# Sheet1.net
KiCad netlist of a schematic drawn in Altium Designer
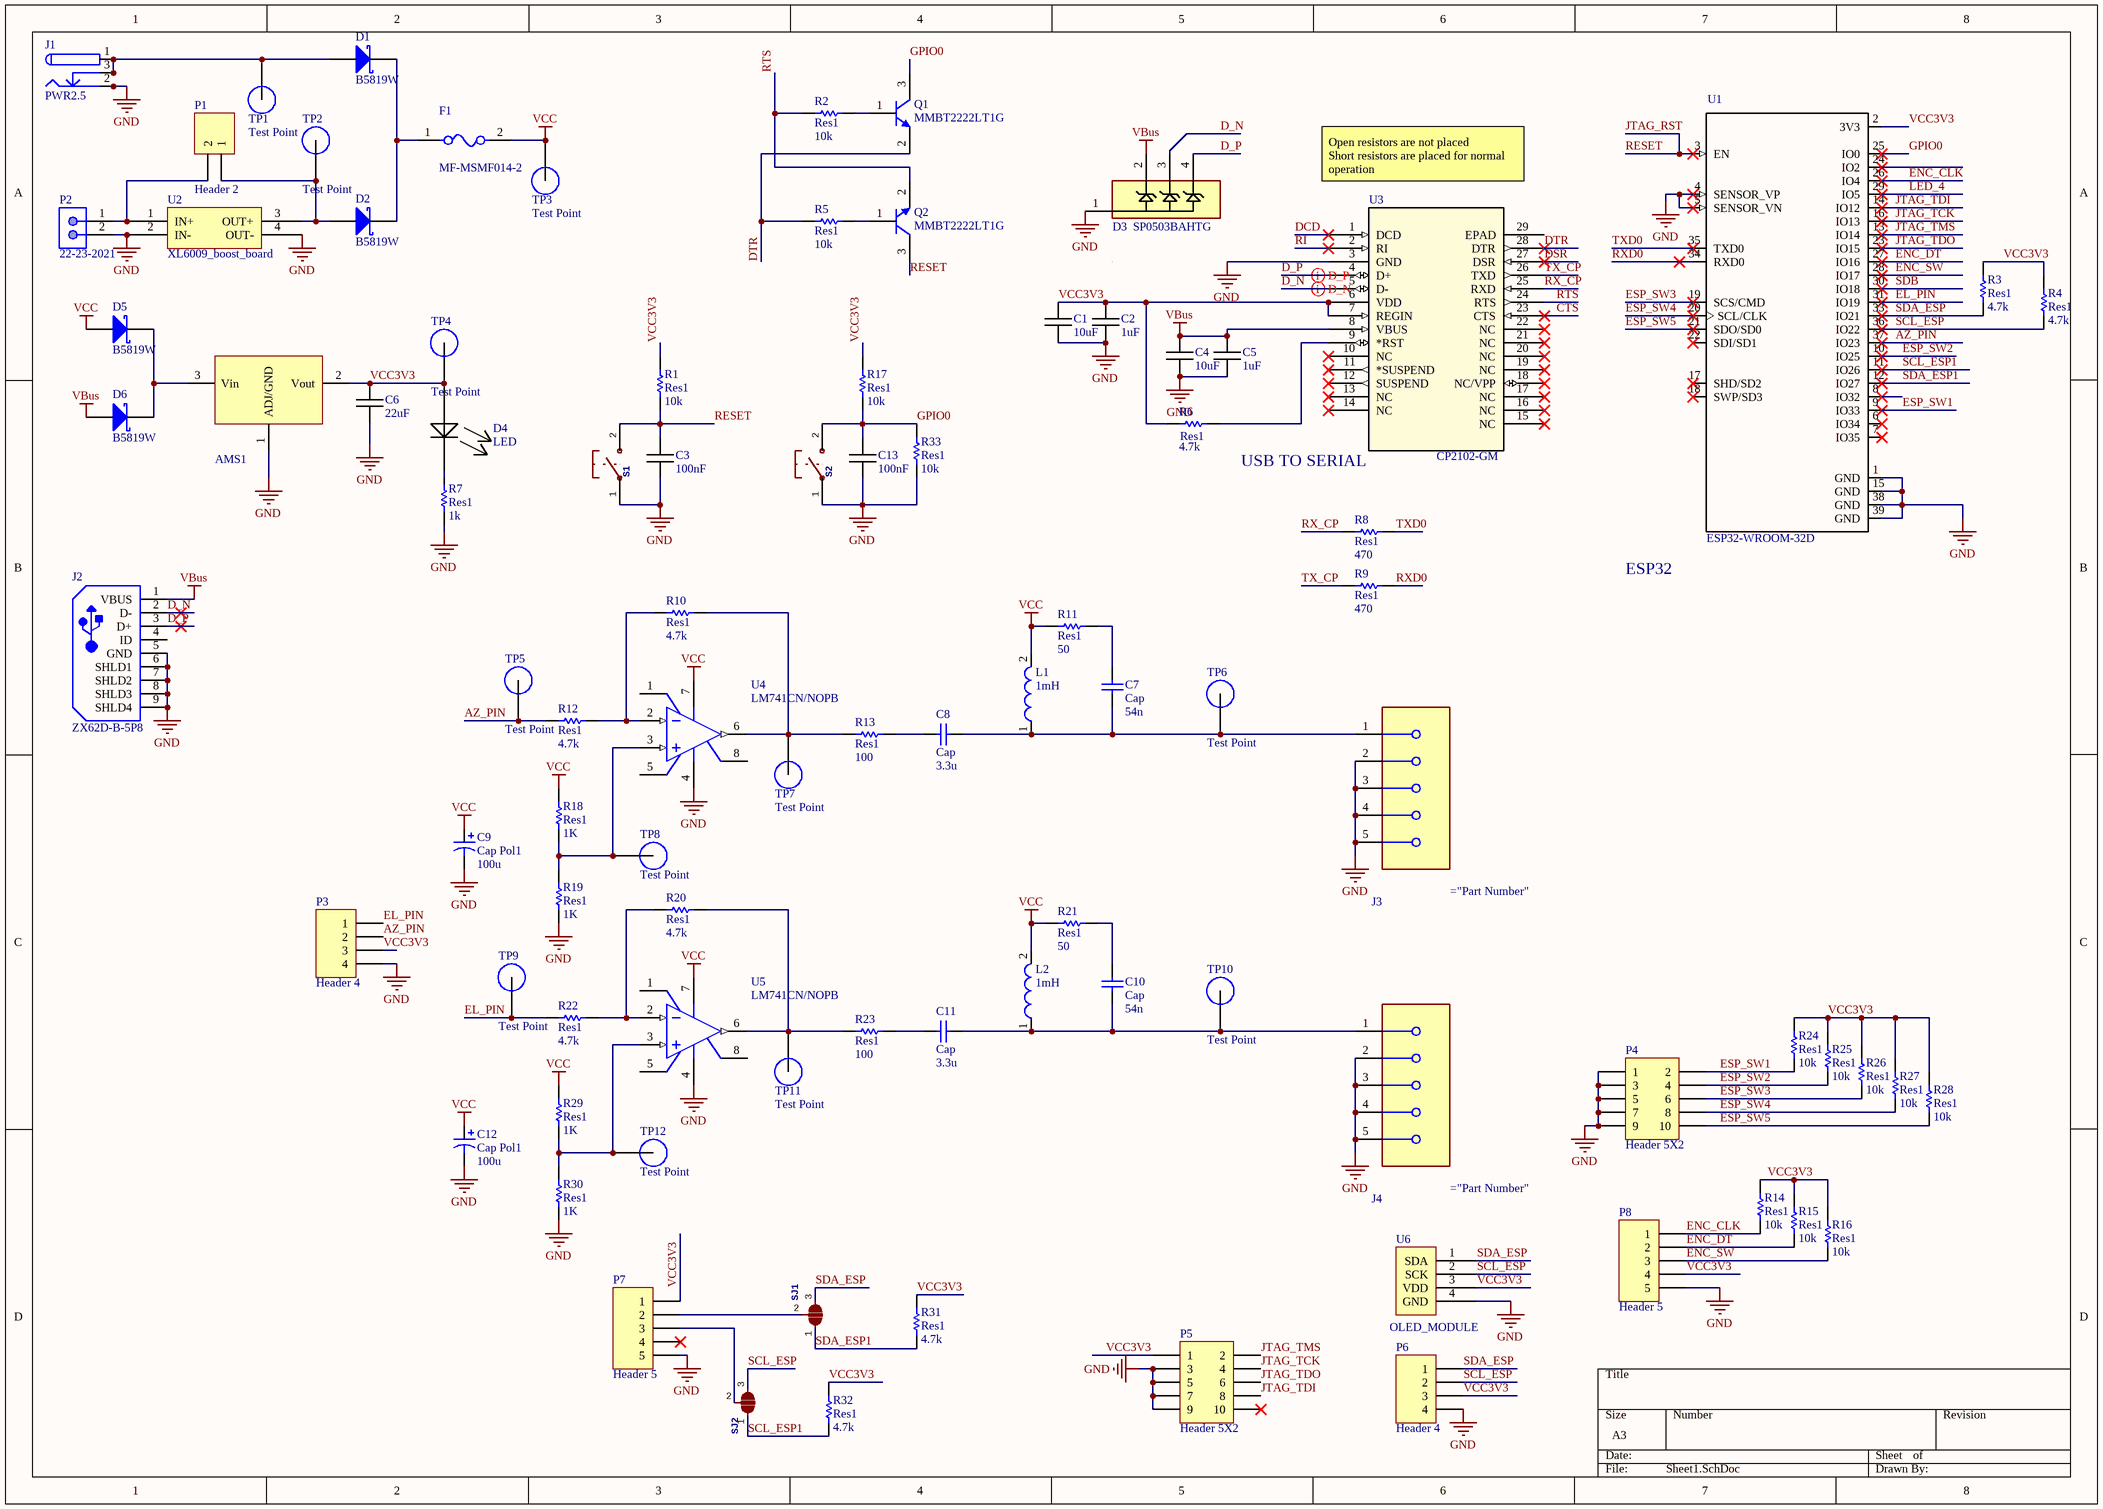
[diagram p0: Sheet1.SchDoc]

(export (version "E")
  (design (tool "Eeschema 10.0.6"))
  (components
    (comp (ref "AMS1")
      (value "AMS1117")
      (footprint "SOT-223-3")
      (description "LDO 3.3V/5V/12V")
      (libsource (lib "IC") (part "AMS1117"))
    )
    (comp (ref "C1")
      (value "10uF")
      (footprint "C 0603 / 1608")
      (libsource (lib "Standard") (part "Capacitor"))
    )
    (comp (ref "C2")
      (value "1uF")
      (footprint "C 0603 / 1608")
      (libsource (lib "Standard") (part "Capacitor"))
    )
    (comp (ref "C3")
      (value "100nF")
      (footprint "C 0603 / 1608")
      (libsource (lib "Standard") (part "Capacitor"))
    )
    (comp (ref "C4")
      (value "10uF")
      (footprint "C 0603 / 1608")
      (libsource (lib "Standard") (part "Capacitor"))
    )
    (comp (ref "C5")
      (value "1uF")
      (footprint "C 0603 / 1608")
      (libsource (lib "Standard") (part "Capacitor"))
    )
    (comp (ref "C6")
      (value "22uF")
      (footprint "C 0603 / 1608")
      (libsource (lib "Standard") (part "Capacitor"))
    )
    (comp (ref "C7")
      (value "Cap")
      (footprint "C 0603 / 1608")
      (description "Capacitor")
      (fields (field (name "ALTIUM_VALUE") "54n") (field (name "PUBLISHER") "Altium Limited"))
      (libsource (lib "Standard") (part "Cap"))
    )
    (comp (ref "C8")
      (value "Cap")
      (footprint "C 0603 / 1608")
      (description "Capacitor")
      (fields (field (name "ALTIUM_VALUE") "3.3u") (field (name "PUBLISHER") "Altium Limited"))
      (libsource (lib "Standard") (part "Cap"))
    )
    (comp (ref "C9")
      (value "Cap Pol1")
      (footprint "CAP0603R")
      (description "Polarized Capacitor (Radial)")
      (fields (field (name "ALTIUM_VALUE") "100u") (field (name "PUBLISHER") "Altium Limited"))
      (libsource (lib "Miscellaneous Devices") (part "Cap Pol1"))
    )
    (comp (ref "C10")
      (value "Cap")
      (footprint "C 0603 / 1608")
      (description "Capacitor")
      (fields (field (name "ALTIUM_VALUE") "54n") (field (name "PUBLISHER") "Altium Limited"))
      (libsource (lib "Standard") (part "Cap"))
    )
    (comp (ref "C11")
      (value "Cap")
      (footprint "C 0603 / 1608")
      (description "Capacitor")
      (fields (field (name "ALTIUM_VALUE") "3.3u") (field (name "PUBLISHER") "Altium Limited"))
      (libsource (lib "Standard") (part "Cap"))
    )
    (comp (ref "C12")
      (value "Cap Pol1")
      (footprint "CAP0603P")
      (description "Polarized Capacitor (Radial)")
      (fields (field (name "ALTIUM_VALUE") "100u") (field (name "PUBLISHER") "Altium Limited"))
      (libsource (lib "Miscellaneous Devices") (part "Cap Pol1"))
    )
    (comp (ref "C13")
      (value "100nF")
      (footprint "C 0603 / 1608")
      (libsource (lib "Standard") (part "Capacitor"))
    )
    (comp (ref "D1")
      (value "B5819W")
      (footprint "MCC-SOD123_V")
      (description "Schottky Barrier Rectifier, 1 A, 40 Vrm, -65 to 125 degC, 2-Pin SOD123, RoHS, Tape and Reel")
      (fields (field (name "MANUFACTURER") "Micro Commercial Components"))
      (libsource (lib "Altium Content Vault") (part "DSKY-AK-2"))
    )
    (comp (ref "D2")
      (value "B5819W")
      (footprint "MCC-SOD123_V")
      (description "Schottky Barrier Rectifier, 1 A, 40 Vrm, -65 to 125 degC, 2-Pin SOD123, RoHS, Tape and Reel")
      (fields (field (name "MANUFACTURER") "Micro Commercial Components"))
      (libsource (lib "Altium Content Vault") (part "DSKY-AK-2"))
    )
    (comp (ref "D3")
      (value "Diode_Littelfuse_SP0503BAHTG_eec")
      (footprint "Littelfuse_SP0503BAHTG_0")
      (description "DIODE TVS DIODE 5.5VWM 8.5VC SOT143")
      (fields
        (field (name "MANUFACTURER") "Littelfuse")
        (field (name "MOUSER PART NUMBER") "576-SP0503BAHTG")
        (field (name "PART NUMBER") "SP0503BAHTG")
      )
      (libsource (lib "IC") (part "Diode_Littelfuse_SP0503BAHTG_eec"))
    )
    (comp (ref "D4") (value "LED") (footprint "LED 0603(2)") (libsource (lib "LEDs") (part "LED")))
    (comp (ref "D5")
      (value "B5819W")
      (footprint "MCC-SOD123_V")
      (description "Schottky Barrier Rectifier, 1 A, 40 Vrm, -65 to 125 degC, 2-Pin SOD123, RoHS, Tape and Reel")
      (fields (field (name "MANUFACTURER") "Micro Commercial Components"))
      (libsource (lib "Altium Content Vault") (part "DSKY-AK-2"))
    )
    (comp (ref "D6")
      (value "B5819W")
      (footprint "MCC-SOD123_V")
      (description "Schottky Barrier Rectifier, 1 A, 40 Vrm, -65 to 125 degC, 2-Pin SOD123, RoHS, Tape and Reel")
      (fields (field (name "MANUFACTURER") "Micro Commercial Components"))
      (libsource (lib "Altium Content Vault") (part "DSKY-AK-2"))
    )
    (comp (ref "F1")
      (value "MF-MSMF014-2")
      (footprint "FP-MF-MSMF-1-MFG")
      (description "PTC RESET FUSE 60V 140MA 1812")
      (fields
        (field (name "MANUFACTURER") "Bourns")
        (field (name "OCTOPART") "https://octopart.com/mf-msmf014-2-bourns-70906")
      )
      (libsource (lib "Altium Content Vault") (part "5bcf9b9f640e542cf0359d10258e979"))
    )
    (comp (ref "J1")
      (value "PWR2.5")
      (footprint "Barrel_Jack_5mm")
      (description "Low Voltage Power Supply Connector")
      (fields (field (name "PUBLISHER") "Altium Limited"))
      (libsource (lib "Miscellaneous Connectors") (part "PWR2.5"))
    )
    (comp (ref "J2")
      (value "ZX62D-B-5P8")
      (footprint "HIRO-ZX62D-B-5P8_V")
      (fields (field (name "TOLERANCE") "10%"))
      (libsource (lib "Altium Content Vault") (part "USB-5-4SHLD"))
    )
    (comp (ref "J3")
      (value "5-1634552-1")
      (footprint "TE_5-1634552-1_0")
      (libsource (lib "Conn_TE_5-1634552-1_eec") (part "5-1634552-1"))
    )
    (comp (ref "J4")
      (value "5-1634552-1")
      (footprint "TE_5-1634552-1_0")
      (libsource (lib "Conn_TE_5-1634552-1_eec") (part "5-1634552-1"))
    )
    (comp (ref "L1")
      (value "1mH")
      (footprint "WE-TI-LS")
      (description "Radial Leaded Wire Wound Inductor WE-TI, L = 1000 µH")
      (libsource (lib "Altium Content Vault") (part "PAS-IND-INDUCTOR-2"))
    )
    (comp (ref "L2")
      (value "1mH")
      (footprint "WE-TI-LS")
      (description "Radial Leaded Wire Wound Inductor WE-TI, L = 1000 µH")
      (libsource (lib "Altium Content Vault") (part "PAS-IND-INDUCTOR-2"))
    )
    (comp (ref "P1")
      (value "Header 2")
      (footprint "HDR1X2")
      (description "Header, 2-Pin")
      (fields (field (name "PUBLISHER") "Altium Limited"))
      (libsource (lib "Miscellaneous Connectors") (part "Header 2"))
    )
    (comp (ref "P2")
      (value "22-23-2021")
      (footprint "MOLX-22-23-2021_V")
      (libsource (lib "Altium Content Vault") (part "CN-1P-M-R2"))
    )
    (comp (ref "P3")
      (value "Header 4")
      (footprint "HDR1X4")
      (description "Header, 4-Pin")
      (fields (field (name "PUBLISHER") "Altium Limited"))
      (libsource (lib "Miscellaneous Connectors") (part "Header 4"))
    )
    (comp (ref "P4")
      (value "Header 5X2")
      (footprint "HDR2X5")
      (description "Header, 5-Pin, Dual row")
      (fields (field (name "PUBLISHER") "Altium Limited"))
      (libsource (lib "Miscellaneous Connectors") (part "Header 5X2"))
    )
    (comp (ref "P5")
      (value "Header 5X2")
      (footprint "HDR2X5")
      (description "Header, 5-Pin, Dual row")
      (fields (field (name "PUBLISHER") "Altium Limited"))
      (libsource (lib "Miscellaneous Connectors") (part "Header 5X2"))
    )
    (comp (ref "P6")
      (value "Header 4")
      (footprint "HDR1X4")
      (description "Header, 4-Pin")
      (fields (field (name "PUBLISHER") "Altium Limited"))
      (libsource (lib "Miscellaneous Connectors") (part "Header 4"))
    )
    (comp (ref "P7")
      (value "Header 5")
      (footprint "HDR1X5")
      (description "Header, 5-Pin")
      (fields (field (name "PUBLISHER") "Altium Limited"))
      (libsource (lib "Miscellaneous Connectors") (part "Header 5"))
    )
    (comp (ref "P8")
      (value "Header 5")
      (footprint "HDR1X5")
      (description "Header, 5-Pin")
      (fields (field (name "PUBLISHER") "Altium Limited"))
      (libsource (lib "Miscellaneous Connectors") (part "Header 5"))
    )
    (comp (ref "Q1")
      (value "MMBT2222LT1G")
      (footprint "ONSC-SOT-23-3-318-08_M")
      (description "General Purpose Transistor, NPN, 0.6 A IC Continuous, 3-Pin SOT23, RoHS, Tape and Reel")
      (fields (field (name "MANUFACTURER") "ON Semiconductor"))
      (libsource (lib "Altium Content Vault") (part "ONSC-NPN_B1E2C3-3"))
    )
    (comp (ref "Q2")
      (value "MMBT2222LT1G")
      (footprint "ONSC-SOT-23-3-318-08_M")
      (description "General Purpose Transistor, NPN, 0.6 A IC Continuous, 3-Pin SOT23, RoHS, Tape and Reel")
      (fields (field (name "MANUFACTURER") "ON Semiconductor"))
      (libsource (lib "Altium Content Vault") (part "ONSC-NPN_B1E2C3-3"))
    )
    (comp (ref "R1")
      (value "Res1")
      (footprint "C 0603 / 1608")
      (description "Resistor")
      (fields (field (name "ALTIUM_VALUE") "10k") (field (name "PUBLISHER") "Altium Limited"))
      (libsource (lib "Miscellaneous Devices") (part "Res1"))
    )
    (comp (ref "R2")
      (value "Res1")
      (footprint "C 0603 / 1608")
      (description "Resistor")
      (fields (field (name "ALTIUM_VALUE") "10k") (field (name "PUBLISHER") "Altium Limited"))
      (libsource (lib "Miscellaneous Devices") (part "Res1"))
    )
    (comp (ref "R3")
      (value "Res1")
      (footprint "C 0603 / 1608")
      (description "Resistor")
      (fields (field (name "ALTIUM_VALUE") "4.7k") (field (name "PUBLISHER") "Altium Limited"))
      (libsource (lib "Miscellaneous Devices") (part "Res1"))
    )
    (comp (ref "R4")
      (value "Res1")
      (footprint "C 0603 / 1608")
      (description "Resistor")
      (fields (field (name "ALTIUM_VALUE") "4.7k") (field (name "PUBLISHER") "Altium Limited"))
      (libsource (lib "Miscellaneous Devices") (part "Res1"))
    )
    (comp (ref "R5")
      (value "Res1")
      (footprint "C 0603 / 1608")
      (description "Resistor")
      (fields (field (name "ALTIUM_VALUE") "10k") (field (name "PUBLISHER") "Altium Limited"))
      (libsource (lib "Miscellaneous Devices") (part "Res1"))
    )
    (comp (ref "R6")
      (value "Res1")
      (footprint "C 0603 / 1608")
      (description "Resistor")
      (fields (field (name "ALTIUM_VALUE") "4.7k") (field (name "PUBLISHER") "Altium Limited"))
      (libsource (lib "Miscellaneous Devices") (part "Res1"))
    )
    (comp (ref "R7")
      (value "Res1")
      (footprint "C 0603 / 1608")
      (description "Resistor")
      (fields (field (name "ALTIUM_VALUE") "1k") (field (name "PUBLISHER") "Altium Limited"))
      (libsource (lib "Miscellaneous Devices") (part "Res1"))
    )
    (comp (ref "R8")
      (value "Res1")
      (footprint "C 0603 / 1608")
      (description "Resistor")
      (fields (field (name "ALTIUM_VALUE") "470") (field (name "PUBLISHER") "Altium Limited"))
      (libsource (lib "Miscellaneous Devices") (part "Res1"))
    )
    (comp (ref "R9")
      (value "Res1")
      (footprint "C 0603 / 1608")
      (description "Resistor")
      (fields (field (name "ALTIUM_VALUE") "470") (field (name "PUBLISHER") "Altium Limited"))
      (libsource (lib "Miscellaneous Devices") (part "Res1"))
    )
    (comp (ref "R10")
      (value "Res1")
      (footprint "RES0603R")
      (description "Resistor")
      (fields (field (name "ALTIUM_VALUE") "4.7k") (field (name "PUBLISHER") "Altium Limited"))
      (libsource (lib "Standard") (part "Res1"))
    )
    (comp (ref "R11")
      (value "Res1")
      (footprint "RES0603R")
      (description "Resistor")
      (fields (field (name "ALTIUM_VALUE") "50") (field (name "PUBLISHER") "Altium Limited"))
      (libsource (lib "Standard") (part "Res1"))
    )
    (comp (ref "R12")
      (value "Res1")
      (footprint "RES0603R")
      (description "Resistor")
      (fields (field (name "ALTIUM_VALUE") "4.7k") (field (name "PUBLISHER") "Altium Limited"))
      (libsource (lib "Standard") (part "Res1"))
    )
    (comp (ref "R13")
      (value "Res1")
      (footprint "RES0603R")
      (description "Resistor")
      (fields (field (name "ALTIUM_VALUE") "100") (field (name "PUBLISHER") "Altium Limited"))
      (libsource (lib "Standard") (part "Res1"))
    )
    (comp (ref "R14")
      (value "Res1")
      (footprint "C 0603 / 1608")
      (description "Resistor")
      (fields (field (name "ALTIUM_VALUE") "10k") (field (name "PUBLISHER") "Altium Limited"))
      (libsource (lib "Miscellaneous Devices") (part "Res1"))
    )
    (comp (ref "R15")
      (value "Res1")
      (footprint "C 0603 / 1608")
      (description "Resistor")
      (fields (field (name "ALTIUM_VALUE") "10k") (field (name "PUBLISHER") "Altium Limited"))
      (libsource (lib "Miscellaneous Devices") (part "Res1"))
    )
    (comp (ref "R16")
      (value "Res1")
      (footprint "C 0603 / 1608")
      (description "Resistor")
      (fields (field (name "ALTIUM_VALUE") "10k") (field (name "PUBLISHER") "Altium Limited"))
      (libsource (lib "Miscellaneous Devices") (part "Res1"))
    )
    (comp (ref "R17")
      (value "Res1")
      (footprint "C 0603 / 1608")
      (description "Resistor")
      (fields (field (name "ALTIUM_VALUE") "10k") (field (name "PUBLISHER") "Altium Limited"))
      (libsource (lib "Miscellaneous Devices") (part "Res1"))
    )
    (comp (ref "R18")
      (value "Res1")
      (footprint "RES0603R")
      (description "Resistor")
      (fields (field (name "ALTIUM_VALUE") "1K") (field (name "PUBLISHER") "Altium Limited"))
      (libsource (lib "Standard") (part "Res1"))
    )
    (comp (ref "R19")
      (value "Res1")
      (footprint "RES0603R")
      (description "Resistor")
      (fields (field (name "ALTIUM_VALUE") "1K") (field (name "PUBLISHER") "Altium Limited"))
      (libsource (lib "Standard") (part "Res1"))
    )
    (comp (ref "R20")
      (value "Res1")
      (footprint "RES0603R")
      (description "Resistor")
      (fields (field (name "ALTIUM_VALUE") "4.7k") (field (name "PUBLISHER") "Altium Limited"))
      (libsource (lib "Standard") (part "Res1"))
    )
    (comp (ref "R21")
      (value "Res1")
      (footprint "RES0603R")
      (description "Resistor")
      (fields (field (name "ALTIUM_VALUE") "50") (field (name "PUBLISHER") "Altium Limited"))
      (libsource (lib "Standard") (part "Res1"))
    )
    (comp (ref "R22")
      (value "Res1")
      (footprint "RES0603R")
      (description "Resistor")
      (fields (field (name "ALTIUM_VALUE") "4.7k") (field (name "PUBLISHER") "Altium Limited"))
      (libsource (lib "Standard") (part "Res1"))
    )
    (comp (ref "R23")
      (value "Res1")
      (footprint "RES0603R")
      (description "Resistor")
      (fields (field (name "ALTIUM_VALUE") "100") (field (name "PUBLISHER") "Altium Limited"))
      (libsource (lib "Standard") (part "Res1"))
    )
    (comp (ref "R24")
      (value "Res1")
      (footprint "C 0603 / 1608")
      (description "Resistor")
      (fields (field (name "ALTIUM_VALUE") "10k") (field (name "PUBLISHER") "Altium Limited"))
      (libsource (lib "Miscellaneous Devices") (part "Res1"))
    )
    (comp (ref "R25")
      (value "Res1")
      (footprint "C 0603 / 1608")
      (description "Resistor")
      (fields (field (name "ALTIUM_VALUE") "10k") (field (name "PUBLISHER") "Altium Limited"))
      (libsource (lib "Miscellaneous Devices") (part "Res1"))
    )
    (comp (ref "R26")
      (value "Res1")
      (footprint "C 0603 / 1608")
      (description "Resistor")
      (fields (field (name "ALTIUM_VALUE") "10k") (field (name "PUBLISHER") "Altium Limited"))
      (libsource (lib "Miscellaneous Devices") (part "Res1"))
    )
    (comp (ref "R27")
      (value "Res1")
      (footprint "C 0603 / 1608")
      (description "Resistor")
      (fields (field (name "ALTIUM_VALUE") "10k") (field (name "PUBLISHER") "Altium Limited"))
      (libsource (lib "Miscellaneous Devices") (part "Res1"))
    )
    (comp (ref "R28")
      (value "Res1")
      (footprint "C 0603 / 1608")
      (description "Resistor")
      (fields (field (name "ALTIUM_VALUE") "10k") (field (name "PUBLISHER") "Altium Limited"))
      (libsource (lib "Miscellaneous Devices") (part "Res1"))
    )
    (comp (ref "R29")
      (value "Res1")
      (footprint "RES0603R")
      (description "Resistor")
      (fields (field (name "ALTIUM_VALUE") "1K") (field (name "PUBLISHER") "Altium Limited"))
      (libsource (lib "Standard") (part "Res1"))
    )
    (comp (ref "R30")
      (value "Res1")
      (footprint "RES0603R")
      (description "Resistor")
      (fields (field (name "ALTIUM_VALUE") "1K") (field (name "PUBLISHER") "Altium Limited"))
      (libsource (lib "Standard") (part "Res1"))
    )
    (comp (ref "R31")
      (value "Res1")
      (footprint "C 0603 / 1608")
      (description "Resistor")
      (fields (field (name "ALTIUM_VALUE") "4.7k") (field (name "PUBLISHER") "Altium Limited"))
      (libsource (lib "Miscellaneous Devices") (part "Res1"))
    )
    (comp (ref "R32")
      (value "Res1")
      (footprint "C 0603 / 1608")
      (description "Resistor")
      (fields (field (name "ALTIUM_VALUE") "4.7k") (field (name "PUBLISHER") "Altium Limited"))
      (libsource (lib "Miscellaneous Devices") (part "Res1"))
    )
    (comp (ref "R33")
      (value "Res1")
      (footprint "C 0603 / 1608")
      (description "Resistor")
      (fields (field (name "ALTIUM_VALUE") "10k") (field (name "PUBLISHER") "Altium Limited"))
      (libsource (lib "Miscellaneous Devices") (part "Res1"))
    )
    (comp (ref "S1")
      (value "Switch")
      (footprint "PUSH_SMD_3x4")
      (fields (field (name "MANUFACTURER") "Omron") (field (name "MPN") "B3U-1000P"))
      (libsource (lib "Switches") (part "B3U-1000P"))
    )
    (comp (ref "S2")
      (value "Switch")
      (footprint "PUSH_SMD_3x4")
      (fields (field (name "MANUFACTURER") "Omron") (field (name "MPN") "B3U-1000P"))
      (libsource (lib "Switches") (part "B3U-1000P"))
    )
    (comp (ref "SJ1")
      (value "2-Way Solder Jumper")
      (footprint "SOLDERJUMPER_2WAY_OPEN_NOPASTE")
      (libsource (lib "Standard2") (part "SOLDERJUMPER_2WAY"))
    )
    (comp (ref "SJ2")
      (value "2-Way Solder Jumper")
      (footprint "SOLDERJUMPER_2WAY_OPEN_NOPASTE")
      (libsource (lib "Standard2") (part "SOLDERJUMPER_2WAY"))
    )
    (comp (ref "TP1")
      (value "Test Point")
      (footprint "Test POint")
      (libsource (lib "Standard") (part "Test Point"))
    )
    (comp (ref "TP2")
      (value "Test Point")
      (footprint "Test POint")
      (libsource (lib "Standard") (part "Test Point"))
    )
    (comp (ref "TP3")
      (value "Test Point")
      (footprint "Test POint")
      (libsource (lib "Standard") (part "Test Point"))
    )
    (comp (ref "TP4")
      (value "Test Point")
      (footprint "Test POint")
      (libsource (lib "Standard") (part "Test Point"))
    )
    (comp (ref "TP5")
      (value "Test Point")
      (footprint "Test POint")
      (libsource (lib "Standard") (part "Test Point"))
    )
    (comp (ref "TP6")
      (value "Test Point")
      (footprint "Test POint")
      (libsource (lib "Standard") (part "Test Point"))
    )
    (comp (ref "TP7")
      (value "Test Point")
      (footprint "Test POint")
      (libsource (lib "Standard") (part "Test Point"))
    )
    (comp (ref "TP8")
      (value "Test Point")
      (footprint "Test POint")
      (libsource (lib "Standard") (part "Test Point"))
    )
    (comp (ref "TP9")
      (value "Test Point")
      (footprint "Test POint")
      (libsource (lib "Standard") (part "Test Point"))
    )
    (comp (ref "TP10")
      (value "Test Point")
      (footprint "Test POint")
      (libsource (lib "Standard") (part "Test Point"))
    )
    (comp (ref "TP11")
      (value "Test Point")
      (footprint "Test POint")
      (libsource (lib "Standard") (part "Test Point"))
    )
    (comp (ref "TP12")
      (value "Test Point")
      (footprint "Test POint")
      (libsource (lib "Standard") (part "Test Point"))
    )
    (comp (ref "U1")
      (value "ESP32-WROOM-32D")
      (footprint "MODULE_ESP32-WROOM-32D")
      (description "IC: SoC; GPIO, I2C, I2S, IR, SD, SDIO, SPI, UART; 2.7Ã·3.6VDC; 20dBm")
      (fields (field (name "MF") "Espressif Systems"))
      (libsource (lib "Arduino") (part "ESP32-WROOM-32D"))
    )
    (comp (ref "U2")
      (value "XL6009_boost_board")
      (footprint "XL6009_board")
      (libsource (lib "XL6009") (part "XL6009_boost_board"))
    )
    (comp (ref "U3")
      (value "CP2102-GM")
      (footprint "QFN28_5X5")
      (description "No Description Available")
      (fields (field (name "COPYRIGHT") "Copyright (C) 2018 Accelerated Designs. All rights reserved"))
      (libsource (lib "IC") (part "CP2102-GM"))
    )
    (comp (ref "U4")
      (value "LM741CN/NOPB")
      (footprint "P0008A")
      (description "Operational Amplifier, 8-pin MDIP, Pb-Free")
      (fields (field (name "MANUFACTURER") "Texas Instruments"))
      (libsource (lib "Altium Content Vault") (part "AMP-OPA-LM741-8"))
    )
    (comp (ref "U5")
      (value "LM741CN/NOPB")
      (footprint "P0008A")
      (description "Operational Amplifier, 8-pin MDIP, Pb-Free")
      (fields (field (name "MANUFACTURER") "Texas Instruments"))
      (libsource (lib "Altium Content Vault") (part "AMP-OPA-LM741-8"))
    )
    (comp (ref "U6")
      (value "OLED_MODULE")
      (footprint "OLED_MODULE")
      (libsource (lib "Conn_TE_5-1634552-1_eec") (part "OLED_MODULE"))
    )
  )
  (nets
    (net (code "1") (name "/AZ_PIN") (class "Default")
      (node (ref "P3") (pin "2") (pinfunction "2_2") (pintype "passive"))
      (node (ref "R12") (pin "1") (pinfunction "1_1") (pintype "passive"))
      (node (ref "TP5") (pin "1") (pintype "passive"))
      (node (ref "U1") (pin "37") (pinfunction "IO23_37") (pintype "bidirectional"))
    )
    (net (code "2") (name "/CTS") (class "Default")
      (node (ref "U3") (pin "23") (pinfunction "CTS_23") (pintype "input+no_connect"))
    )
    (net (code "3") (name "/DCD") (class "Default")
      (node (ref "U3") (pin "1") (pinfunction "DCD_1") (pintype "input+no_connect"))
    )
    (net (code "4") (name "/DSR") (class "Default")
      (node (ref "U3") (pin "27") (pinfunction "DSR_27") (pintype "input+no_connect"))
    )
    (net (code "5") (name "/DTR") (class "Default")
      (node (ref "Q1") (pin "2") (pinfunction "E_2") (pintype "passive"))
      (node (ref "R5") (pin "1") (pinfunction "1_1") (pintype "passive"))
      (node (ref "U3") (pin "28") (pinfunction "DTR_28") (pintype "output"))
    )
    (net (code "6") (name "/D_N") (class "Default")
      (node (ref "D3") (pin "3") (pinfunction "2_CATHODE_3") (pintype "passive"))
      (node (ref "J2") (pin "2") (pinfunction "D-_2") (pintype "passive"))
      (node (ref "U3") (pin "5") (pinfunction "D-_5") (pintype "bidirectional"))
    )
    (net (code "7") (name "/D_P") (class "Default")
      (node (ref "D3") (pin "4") (pinfunction "3_CATHODE_4") (pintype "passive"))
      (node (ref "J2") (pin "3") (pinfunction "D+_3") (pintype "passive"))
      (node (ref "U3") (pin "4") (pinfunction "D+_4") (pintype "bidirectional"))
    )
    (net (code "8") (name "/EL_PIN") (class "Default")
      (node (ref "P3") (pin "1") (pinfunction "1_1") (pintype "passive"))
      (node (ref "R22") (pin "1") (pinfunction "1_1") (pintype "passive"))
      (node (ref "TP9") (pin "1") (pintype "passive"))
      (node (ref "U1") (pin "31") (pinfunction "IO19_31") (pintype "bidirectional"))
    )
    (net (code "9") (name "/ENC_CLK") (class "Default")
      (node (ref "P8") (pin "1") (pinfunction "1_1") (pintype "passive"))
      (node (ref "R14") (pin "1") (pinfunction "1_1") (pintype "passive"))
      (node (ref "U1") (pin "26") (pinfunction "IO4_26") (pintype "bidirectional"))
    )
    (net (code "10") (name "/ENC_DT") (class "Default")
      (node (ref "P8") (pin "2") (pinfunction "2_2") (pintype "passive"))
      (node (ref "R15") (pin "1") (pinfunction "1_1") (pintype "passive"))
      (node (ref "U1") (pin "27") (pinfunction "IO16_27") (pintype "bidirectional"))
    )
    (net (code "11") (name "/ENC_SW") (class "Default")
      (node (ref "P8") (pin "3") (pinfunction "3_3") (pintype "passive"))
      (node (ref "R16") (pin "1") (pinfunction "1_1") (pintype "passive"))
      (node (ref "U1") (pin "28") (pinfunction "IO17_28") (pintype "bidirectional"))
    )
    (net (code "12") (name "/ESP_SW1") (class "Default")
      (node (ref "P4") (pin "2") (pinfunction "2_2") (pintype "passive"))
      (node (ref "R24") (pin "1") (pinfunction "1_1") (pintype "passive"))
      (node (ref "U1") (pin "9") (pinfunction "IO33_9") (pintype "bidirectional"))
    )
    (net (code "13") (name "/ESP_SW2") (class "Default")
      (node (ref "P4") (pin "4") (pinfunction "4_4") (pintype "passive"))
      (node (ref "R25") (pin "1") (pinfunction "1_1") (pintype "passive"))
      (node (ref "U1") (pin "10") (pinfunction "IO25_10") (pintype "bidirectional"))
    )
    (net (code "14") (name "/ESP_SW3") (class "Default")
      (node (ref "P4") (pin "6") (pinfunction "6_6") (pintype "passive"))
      (node (ref "R26") (pin "1") (pinfunction "1_1") (pintype "passive"))
      (node (ref "U1") (pin "19") (pinfunction "SCS/CMD_19") (pintype "bidirectional"))
    )
    (net (code "15") (name "/ESP_SW4") (class "Default")
      (node (ref "P4") (pin "8") (pinfunction "8_8") (pintype "passive"))
      (node (ref "R27") (pin "1") (pinfunction "1_1") (pintype "passive"))
      (node (ref "U1") (pin "20") (pinfunction "SCL/CLK_20") (pintype "bidirectional"))
    )
    (net (code "16") (name "/ESP_SW5") (class "Default")
      (node (ref "P4") (pin "10") (pinfunction "10_10") (pintype "passive"))
      (node (ref "R28") (pin "1") (pinfunction "1_1") (pintype "passive"))
      (node (ref "U1") (pin "21") (pinfunction "SDO/SD0_21") (pintype "bidirectional"))
    )
    (net (code "17") (name "/GPIO0") (class "Default")
      (node (ref "C13") (pin "1") (pinfunction "1_1") (pintype "passive"))
      (node (ref "Q1") (pin "3") (pinfunction "C_3") (pintype "passive"))
      (node (ref "R17") (pin "2") (pinfunction "2_2") (pintype "passive"))
      (node (ref "R33") (pin "1") (pinfunction "1_1") (pintype "passive"))
      (node (ref "S2") (pin "2") (pinfunction "P$2_2") (pintype "passive"))
      (node (ref "U1") (pin "25") (pinfunction "IO0_25") (pintype "bidirectional"))
    )
    (net (code "18") (name "/JTAG_RST") (class "Default")
      (node (ref "C3") (pin "1") (pinfunction "1_1") (pintype "passive"))
      (node (ref "Q2") (pin "3") (pinfunction "C_3") (pintype "passive"))
      (node (ref "R1") (pin "2") (pinfunction "2_2") (pintype "passive"))
      (node (ref "S1") (pin "2") (pinfunction "P$2_2") (pintype "passive"))
      (node (ref "U1") (pin "3") (pinfunction "EN_3") (pintype "input"))
    )
    (net (code "19") (name "/JTAG_TCK") (class "Default")
      (node (ref "P5") (pin "4") (pinfunction "4_4") (pintype "passive"))
      (node (ref "U1") (pin "16") (pinfunction "IO13_16") (pintype "bidirectional"))
    )
    (net (code "20") (name "/JTAG_TDI") (class "Default")
      (node (ref "P5") (pin "8") (pinfunction "8_8") (pintype "passive"))
      (node (ref "U1") (pin "14") (pinfunction "IO12_14") (pintype "bidirectional"))
    )
    (net (code "21") (name "/JTAG_TDO") (class "Default")
      (node (ref "P5") (pin "6") (pinfunction "6_6") (pintype "passive"))
      (node (ref "U1") (pin "23") (pinfunction "IO15_23") (pintype "bidirectional"))
    )
    (net (code "22") (name "/JTAG_TMS") (class "Default")
      (node (ref "P5") (pin "2") (pinfunction "2_2") (pintype "passive"))
      (node (ref "U1") (pin "13") (pinfunction "IO14_13") (pintype "bidirectional"))
    )
    (net (code "23") (name "/LED_4") (class "Default")
      (node (ref "U1") (pin "29") (pinfunction "IO5_29") (pintype "bidirectional+no_connect"))
    )
    (net (code "24") (name "/RI") (class "Default")
      (node (ref "U3") (pin "2") (pinfunction "RI_2") (pintype "input+no_connect"))
    )
    (net (code "25") (name "/RTS") (class "Default")
      (node (ref "Q2") (pin "2") (pinfunction "E_2") (pintype "passive"))
      (node (ref "R2") (pin "1") (pinfunction "1_1") (pintype "passive"))
      (node (ref "U3") (pin "24") (pinfunction "RTS_24") (pintype "output"))
    )
    (net (code "26") (name "/RXD0") (class "Default")
      (node (ref "R9") (pin "2") (pinfunction "2_2") (pintype "passive"))
      (node (ref "U1") (pin "34") (pinfunction "RXD0_34") (pintype "bidirectional"))
    )
    (net (code "27") (name "/RX_CP") (class "Default")
      (node (ref "R8") (pin "1") (pinfunction "1_1") (pintype "passive"))
      (node (ref "U3") (pin "25") (pinfunction "RXD_25") (pintype "input"))
    )
    (net (code "28") (name "/SCL_ESP") (class "Default")
      (node (ref "P6") (pin "2") (pinfunction "2_2") (pintype "passive"))
      (node (ref "R4") (pin "2") (pinfunction "2_2") (pintype "passive"))
      (node (ref "SJ2") (pin "3") (pinfunction "3_3") (pintype "passive"))
      (node (ref "U1") (pin "36") (pinfunction "IO22_36") (pintype "bidirectional"))
      (node (ref "U6") (pin "2") (pinfunction "SCK_2") (pintype "passive"))
    )
    (net (code "29") (name "/SCL_ESP1") (class "Default")
      (node (ref "R32") (pin "2") (pinfunction "2_2") (pintype "passive"))
      (node (ref "SJ2") (pin "1") (pinfunction "1_1") (pintype "passive"))
      (node (ref "U1") (pin "11") (pinfunction "IO26_11") (pintype "bidirectional"))
    )
    (net (code "30") (name "/SDA_ESP") (class "Default")
      (node (ref "P6") (pin "1") (pinfunction "1_1") (pintype "passive"))
      (node (ref "R3") (pin "2") (pinfunction "2_2") (pintype "passive"))
      (node (ref "SJ1") (pin "3") (pinfunction "3_3") (pintype "passive"))
      (node (ref "U1") (pin "33") (pinfunction "IO21_33") (pintype "bidirectional"))
      (node (ref "U6") (pin "1") (pinfunction "SDA_1") (pintype "passive"))
    )
    (net (code "31") (name "/SDA_ESP1") (class "Default")
      (node (ref "R31") (pin "2") (pinfunction "2_2") (pintype "passive"))
      (node (ref "SJ1") (pin "1") (pinfunction "1_1") (pintype "passive"))
      (node (ref "U1") (pin "12") (pinfunction "IO27_12") (pintype "bidirectional"))
    )
    (net (code "32") (name "/SDB") (class "Default")
      (node (ref "U1") (pin "30") (pinfunction "IO18_30") (pintype "bidirectional+no_connect"))
    )
    (net (code "33") (name "/TXD0") (class "Default")
      (node (ref "R8") (pin "2") (pinfunction "2_2") (pintype "passive"))
      (node (ref "U1") (pin "35") (pinfunction "TXD0_35") (pintype "bidirectional"))
    )
    (net (code "34") (name "/TX_CP") (class "Default")
      (node (ref "R9") (pin "1") (pinfunction "1_1") (pintype "passive"))
      (node (ref "U3") (pin "26") (pinfunction "TXD_26") (pintype "output"))
    )
    (net (code "35") (name "/VCC3V3") (class "Default")
      (node (ref "AMS1") (pin "2") (pinfunction "Vout_2") (pintype "passive"))
      (node (ref "C1") (pin "2") (pinfunction "1_2") (pintype "passive"))
      (node (ref "C2") (pin "2") (pinfunction "1_2") (pintype "passive"))
      (node (ref "C6") (pin "2") (pinfunction "1_2") (pintype "passive"))
      (node (ref "D4") (pin "1") (pinfunction "+_1") (pintype "passive"))
      (node (ref "P3") (pin "3") (pinfunction "3_3") (pintype "passive"))
      (node (ref "P5") (pin "1") (pinfunction "1_1") (pintype "passive"))
      (node (ref "P6") (pin "3") (pinfunction "3_3") (pintype "passive"))
      (node (ref "P7") (pin "1") (pinfunction "1_1") (pintype "passive"))
      (node (ref "P8") (pin "4") (pinfunction "4_4") (pintype "passive"))
      (node (ref "R1") (pin "1") (pinfunction "1_1") (pintype "passive"))
      (node (ref "R14") (pin "2") (pinfunction "2_2") (pintype "passive"))
      (node (ref "R15") (pin "2") (pinfunction "2_2") (pintype "passive"))
      (node (ref "R16") (pin "2") (pinfunction "2_2") (pintype "passive"))
      (node (ref "R17") (pin "1") (pinfunction "1_1") (pintype "passive"))
      (node (ref "R24") (pin "2") (pinfunction "2_2") (pintype "passive"))
      (node (ref "R25") (pin "2") (pinfunction "2_2") (pintype "passive"))
      (node (ref "R26") (pin "2") (pinfunction "2_2") (pintype "passive"))
      (node (ref "R27") (pin "2") (pinfunction "2_2") (pintype "passive"))
      (node (ref "R28") (pin "2") (pinfunction "2_2") (pintype "passive"))
      (node (ref "R3") (pin "1") (pinfunction "1_1") (pintype "passive"))
      (node (ref "R31") (pin "1") (pinfunction "1_1") (pintype "passive"))
      (node (ref "R32") (pin "1") (pinfunction "1_1") (pintype "passive"))
      (node (ref "R4") (pin "1") (pinfunction "1_1") (pintype "passive"))
      (node (ref "R6") (pin "1") (pinfunction "1_1") (pintype "passive"))
      (node (ref "TP4") (pin "1") (pintype "passive"))
      (node (ref "U1") (pin "2") (pinfunction "3V3_2") (pintype "power_in"))
      (node (ref "U3") (pin "6") (pinfunction "VDD_6") (pintype "power_in"))
      (node (ref "U3") (pin "7") (pinfunction "REGIN_7") (pintype "input"))
      (node (ref "U6") (pin "3") (pinfunction "VDD_3") (pintype "passive"))
    )
    (net (code "36") (name "GND") (class "Default")
      (node (ref "AMS1") (pin "1") (pinfunction "ADJ/GND_1") (pintype "passive"))
      (node (ref "C1") (pin "1") (pinfunction "1_1") (pintype "passive"))
      (node (ref "C12") (pin "2") (pinfunction "2_2") (pintype "passive"))
      (node (ref "C13") (pin "2") (pinfunction "1_2") (pintype "passive"))
      (node (ref "C2") (pin "1") (pinfunction "1_1") (pintype "passive"))
      (node (ref "C3") (pin "2") (pinfunction "1_2") (pintype "passive"))
      (node (ref "C4") (pin "1") (pinfunction "1_1") (pintype "passive"))
      (node (ref "C5") (pin "1") (pinfunction "1_1") (pintype "passive"))
      (node (ref "C6") (pin "1") (pinfunction "1_1") (pintype "passive"))
      (node (ref "C9") (pin "2") (pinfunction "2_2") (pintype "passive"))
      (node (ref "D3") (pin "1") (pinfunction "COMMON_ANODE_1") (pintype "passive"))
      (node (ref "J1") (pin "2") (pinfunction "2_2") (pintype "power_in"))
      (node (ref "J1") (pin "2A") (pinfunction "2A_2A") (pintype "power_in"))
      (node (ref "J1") (pin "2B") (pinfunction "2B_2B") (pintype "power_in"))
      (node (ref "J2") (pin "5") (pinfunction "GND_5") (pintype "passive"))
      (node (ref "J2") (pin "6") (pinfunction "SHLD1_6") (pintype "passive"))
      (node (ref "J2") (pin "7") (pinfunction "SHLD2_7") (pintype "passive"))
      (node (ref "J2") (pin "8") (pinfunction "SHLD3_8") (pintype "passive"))
      (node (ref "J2") (pin "9") (pinfunction "SHLD4_9") (pintype "passive"))
      (node (ref "J3") (pin "2") (pinfunction "MNT_1_2") (pintype "passive"))
      (node (ref "J3") (pin "3") (pinfunction "MNT_2_3") (pintype "passive"))
      (node (ref "J3") (pin "4") (pinfunction "MNT_3_4") (pintype "passive"))
      (node (ref "J3") (pin "5") (pinfunction "MNT_4_5") (pintype "passive"))
      (node (ref "J4") (pin "2") (pinfunction "MNT_1_2") (pintype "passive"))
      (node (ref "J4") (pin "3") (pinfunction "MNT_2_3") (pintype "passive"))
      (node (ref "J4") (pin "4") (pinfunction "MNT_3_4") (pintype "passive"))
      (node (ref "J4") (pin "5") (pinfunction "MNT_4_5") (pintype "passive"))
      (node (ref "P2") (pin "2") (pinfunction "2_2") (pintype "passive"))
      (node (ref "P3") (pin "4") (pinfunction "4_4") (pintype "passive"))
      (node (ref "P4") (pin "1") (pinfunction "1_1") (pintype "passive"))
      (node (ref "P4") (pin "3") (pinfunction "3_3") (pintype "passive"))
      (node (ref "P4") (pin "5") (pinfunction "5_5") (pintype "passive"))
      (node (ref "P4") (pin "7") (pinfunction "7_7") (pintype "passive"))
      (node (ref "P4") (pin "9") (pinfunction "9_9") (pintype "passive"))
      (node (ref "P5") (pin "3") (pinfunction "3_3") (pintype "passive"))
      (node (ref "P5") (pin "5") (pinfunction "5_5") (pintype "passive"))
      (node (ref "P5") (pin "7") (pinfunction "7_7") (pintype "passive"))
      (node (ref "P5") (pin "9") (pinfunction "9_9") (pintype "passive"))
      (node (ref "P6") (pin "4") (pinfunction "4_4") (pintype "passive"))
      (node (ref "P7") (pin "5") (pinfunction "5_5") (pintype "passive"))
      (node (ref "P8") (pin "5") (pinfunction "5_5") (pintype "passive"))
      (node (ref "R19") (pin "1") (pinfunction "1_1") (pintype "passive"))
      (node (ref "R30") (pin "1") (pinfunction "1_1") (pintype "passive"))
      (node (ref "R33") (pin "2") (pinfunction "2_2") (pintype "passive"))
      (node (ref "R7") (pin "2") (pinfunction "2_2") (pintype "passive"))
      (node (ref "S1") (pin "1") (pinfunction "P$1_1") (pintype "passive"))
      (node (ref "S2") (pin "1") (pinfunction "P$1_1") (pintype "passive"))
      (node (ref "U1") (pin "1") (pinfunction "GND_1") (pintype "power_in"))
      (node (ref "U1") (pin "15") (pinfunction "GND_15") (pintype "power_in"))
      (node (ref "U1") (pin "38") (pinfunction "GND_38") (pintype "power_in"))
      (node (ref "U1") (pin "39") (pinfunction "GND_39") (pintype "power_in"))
      (node (ref "U1") (pin "4") (pinfunction "SENSOR_VP_4") (pintype "input"))
      (node (ref "U1") (pin "5") (pinfunction "SENSOR_VN_5") (pintype "input"))
      (node (ref "U2") (pin "2") (pinfunction "IN-_2") (pintype "passive"))
      (node (ref "U2") (pin "4") (pinfunction "OUT-_4") (pintype "passive"))
      (node (ref "U3") (pin "3") (pinfunction "GND_3") (pintype "power_in"))
      (node (ref "U4") (pin "4") (pinfunction "V-_4") (pintype "power_in"))
      (node (ref "U5") (pin "4") (pinfunction "V-_4") (pintype "power_in"))
      (node (ref "U6") (pin "4") (pinfunction "GND_4") (pintype "passive"))
    )
    (net (code "37") (name "Net-(AMS1-Vin)") (class "Default")
      (node (ref "AMS1") (pin "3") (pinfunction "Vin_3") (pintype "passive"))
      (node (ref "D5") (pin "2") (pinfunction "K_2") (pintype "passive"))
      (node (ref "D6") (pin "2") (pinfunction "K_2") (pintype "passive"))
    )
    (net (code "38") (name "Net-(C7-Pad1)") (class "Default")
      (node (ref "C7") (pin "1") (pinfunction "1_1") (pintype "passive"))
      (node (ref "R11") (pin "1") (pinfunction "1_1") (pintype "passive"))
    )
    (net (code "39") (name "Net-(C7-Pad2)") (class "Default")
      (node (ref "C7") (pin "2") (pinfunction "2_2") (pintype "passive"))
      (node (ref "C8") (pin "2") (pinfunction "2_2") (pintype "passive"))
      (node (ref "J3") (pin "1") (pinfunction "1_1") (pintype "passive"))
      (node (ref "L1") (pin "1") (pinfunction "1_1") (pintype "passive"))
      (node (ref "TP6") (pin "1") (pintype "passive"))
    )
    (net (code "40") (name "Net-(C8-Pad1)") (class "Default")
      (node (ref "C8") (pin "1") (pinfunction "1_1") (pintype "passive"))
      (node (ref "R13") (pin "2") (pinfunction "2_2") (pintype "passive"))
    )
    (net (code "41") (name "Net-(C10-Pad1)") (class "Default")
      (node (ref "C10") (pin "1") (pinfunction "1_1") (pintype "passive"))
      (node (ref "R21") (pin "1") (pinfunction "1_1") (pintype "passive"))
    )
    (net (code "42") (name "Net-(C10-Pad2)") (class "Default")
      (node (ref "C10") (pin "2") (pinfunction "2_2") (pintype "passive"))
      (node (ref "C11") (pin "2") (pinfunction "2_2") (pintype "passive"))
      (node (ref "J4") (pin "1") (pinfunction "1_1") (pintype "passive"))
      (node (ref "L2") (pin "1") (pinfunction "1_1") (pintype "passive"))
      (node (ref "TP10") (pin "1") (pintype "passive"))
    )
    (net (code "43") (name "Net-(C11-Pad1)") (class "Default")
      (node (ref "C11") (pin "1") (pinfunction "1_1") (pintype "passive"))
      (node (ref "R23") (pin "2") (pinfunction "2_2") (pintype "passive"))
    )
    (net (code "44") (name "Net-(D1-A)") (class "Default")
      (node (ref "D1") (pin "1") (pinfunction "A_1") (pintype "passive"))
      (node (ref "J1") (pin "1") (pinfunction "1_1") (pintype "power_in"))
      (node (ref "J1") (pin "1A") (pinfunction "1A_1A") (pintype "power_in"))
      (node (ref "J1") (pin "1B") (pinfunction "1B_1B") (pintype "power_in"))
      (node (ref "J1") (pin "3") (pinfunction "3_3") (pintype "power_in"))
      (node (ref "J1") (pin "3A") (pinfunction "3A_3A") (pintype "power_in"))
      (node (ref "J1") (pin "3B") (pinfunction "3B_3B") (pintype "power_in"))
      (node (ref "TP1") (pin "1") (pintype "passive"))
    )
    (net (code "45") (name "Net-(D1-K)") (class "Default")
      (node (ref "D1") (pin "2") (pinfunction "K_2") (pintype "passive"))
      (node (ref "D2") (pin "2") (pinfunction "K_2") (pintype "passive"))
      (node (ref "F1") (pin "1") (pinfunction "1_1") (pintype "passive"))
    )
    (net (code "46") (name "Net-(D2-A)") (class "Default")
      (node (ref "D2") (pin "1") (pinfunction "A_1") (pintype "passive"))
      (node (ref "P1") (pin "1") (pinfunction "1_1") (pintype "passive"))
      (node (ref "TP2") (pin "1") (pintype "passive"))
      (node (ref "U2") (pin "3") (pinfunction "OUT+_3") (pintype "passive"))
    )
    (net (code "47") (name "Net-(D4--)") (class "Default")
      (node (ref "D4") (pin "2") (pinfunction "-_2") (pintype "passive"))
      (node (ref "R7") (pin "1") (pinfunction "1_1") (pintype "passive"))
    )
    (net (code "48") (name "Net-(P7-Pad2)") (class "Default")
      (node (ref "P7") (pin "2") (pinfunction "2_2") (pintype "passive"))
      (node (ref "SJ1") (pin "2") (pinfunction "2_2") (pintype "passive"))
    )
    (net (code "49") (name "Net-(P7-Pad3)") (class "Default")
      (node (ref "P7") (pin "3") (pinfunction "3_3") (pintype "passive"))
      (node (ref "SJ2") (pin "2") (pinfunction "2_2") (pintype "passive"))
    )
    (net (code "50") (name "Net-(Q1-B)") (class "Default")
      (node (ref "Q1") (pin "1") (pinfunction "B_1") (pintype "passive"))
      (node (ref "R2") (pin "2") (pinfunction "2_2") (pintype "passive"))
    )
    (net (code "51") (name "Net-(Q2-B)") (class "Default")
      (node (ref "Q2") (pin "1") (pinfunction "B_1") (pintype "passive"))
      (node (ref "R5") (pin "2") (pinfunction "2_2") (pintype "passive"))
    )
    (net (code "52") (name "Net-(U2-IN+)") (class "Default")
      (node (ref "P1") (pin "2") (pinfunction "2_2") (pintype "passive"))
      (node (ref "P2") (pin "1") (pinfunction "1_1") (pintype "passive"))
      (node (ref "U2") (pin "1") (pinfunction "IN+_1") (pintype "passive"))
    )
    (net (code "53") (name "Net-(U3-*RST)") (class "Default")
      (node (ref "R6") (pin "2") (pinfunction "2_2") (pintype "passive"))
      (node (ref "U3") (pin "9") (pinfunction "*RST_9") (pintype "bidirectional"))
    )
    (net (code "54") (name "Net-(U4-IN+)") (class "Default")
      (node (ref "R18") (pin "1") (pinfunction "1_1") (pintype "passive"))
      (node (ref "R19") (pin "2") (pinfunction "2_2") (pintype "passive"))
      (node (ref "TP8") (pin "1") (pintype "passive"))
      (node (ref "U4") (pin "3") (pinfunction "IN+_3") (pintype "input"))
    )
    (net (code "55") (name "Net-(U4-IN-)") (class "Default")
      (node (ref "R10") (pin "1") (pinfunction "1_1") (pintype "passive"))
      (node (ref "R12") (pin "2") (pinfunction "2_2") (pintype "passive"))
      (node (ref "U4") (pin "2") (pinfunction "IN-_2") (pintype "input"))
    )
    (net (code "56") (name "Net-(U4-OUT)") (class "Default")
      (node (ref "R10") (pin "2") (pinfunction "2_2") (pintype "passive"))
      (node (ref "R13") (pin "1") (pinfunction "1_1") (pintype "passive"))
      (node (ref "TP7") (pin "1") (pintype "passive"))
      (node (ref "U4") (pin "6") (pinfunction "OUT_6") (pintype "output"))
    )
    (net (code "57") (name "Net-(U5-IN+)") (class "Default")
      (node (ref "R29") (pin "1") (pinfunction "1_1") (pintype "passive"))
      (node (ref "R30") (pin "2") (pinfunction "2_2") (pintype "passive"))
      (node (ref "TP12") (pin "1") (pintype "passive"))
      (node (ref "U5") (pin "3") (pinfunction "IN+_3") (pintype "input"))
    )
    (net (code "58") (name "Net-(U5-IN-)") (class "Default")
      (node (ref "R20") (pin "1") (pinfunction "1_1") (pintype "passive"))
      (node (ref "R22") (pin "2") (pinfunction "2_2") (pintype "passive"))
      (node (ref "U5") (pin "2") (pinfunction "IN-_2") (pintype "input"))
    )
    (net (code "59") (name "Net-(U5-OUT)") (class "Default")
      (node (ref "R20") (pin "2") (pinfunction "2_2") (pintype "passive"))
      (node (ref "R23") (pin "1") (pinfunction "1_1") (pintype "passive"))
      (node (ref "TP11") (pin "1") (pintype "passive"))
      (node (ref "U5") (pin "6") (pinfunction "OUT_6") (pintype "output"))
    )
    (net (code "60") (name "VBus") (class "Default")
      (node (ref "C4") (pin "2") (pinfunction "1_2") (pintype "passive"))
      (node (ref "C5") (pin "2") (pinfunction "1_2") (pintype "passive"))
      (node (ref "D3") (pin "2") (pinfunction "1_CATHODE_2") (pintype "passive"))
      (node (ref "D6") (pin "1") (pinfunction "A_1") (pintype "passive"))
      (node (ref "J2") (pin "1") (pinfunction "VBUS_1") (pintype "passive"))
      (node (ref "U3") (pin "8") (pinfunction "VBUS_8") (pintype "input"))
    )
    (net (code "61") (name "VCC") (class "Default")
      (node (ref "C12") (pin "1") (pinfunction "1_1") (pintype "passive"))
      (node (ref "C9") (pin "1") (pinfunction "1_1") (pintype "passive"))
      (node (ref "D5") (pin "1") (pinfunction "A_1") (pintype "passive"))
      (node (ref "F1") (pin "2") (pinfunction "2_2") (pintype "passive"))
      (node (ref "L1") (pin "2") (pinfunction "2_2") (pintype "passive"))
      (node (ref "L2") (pin "2") (pinfunction "2_2") (pintype "passive"))
      (node (ref "R11") (pin "2") (pinfunction "2_2") (pintype "passive"))
      (node (ref "R18") (pin "2") (pinfunction "2_2") (pintype "passive"))
      (node (ref "R21") (pin "2") (pinfunction "2_2") (pintype "passive"))
      (node (ref "R29") (pin "2") (pinfunction "2_2") (pintype "passive"))
      (node (ref "TP3") (pin "1") (pintype "passive"))
      (node (ref "U4") (pin "7") (pinfunction "V+_7") (pintype "power_in"))
      (node (ref "U5") (pin "7") (pinfunction "V+_7") (pintype "power_in"))
    )
    (net (code "62") (name "unconnected-(J2-ID-Pad4)") (class "Default")
      (node (ref "J2") (pin "4") (pinfunction "ID_4") (pintype "passive"))
    )
    (net (code "63") (name "unconnected-(P5-Pad10)") (class "Default")
      (node (ref "P5") (pin "10") (pinfunction "10_10") (pintype "passive+no_connect"))
    )
    (net (code "64") (name "unconnected-(P7-Pad4)") (class "Default")
      (node (ref "P7") (pin "4") (pinfunction "4_4") (pintype "passive+no_connect"))
    )
    (net (code "65") (name "unconnected-(U1-IO2-Pad24)") (class "Default")
      (node (ref "U1") (pin "24") (pinfunction "IO2_24") (pintype "bidirectional+no_connect"))
    )
    (net (code "66") (name "unconnected-(U1-IO32-Pad8)") (class "Default")
      (node (ref "U1") (pin "8") (pinfunction "IO32_8") (pintype "bidirectional+no_connect"))
    )
    (net (code "67") (name "unconnected-(U1-IO34-Pad6)") (class "Default")
      (node (ref "U1") (pin "6") (pinfunction "IO34_6") (pintype "bidirectional+no_connect"))
    )
    (net (code "68") (name "unconnected-(U1-IO35-Pad7)") (class "Default")
      (node (ref "U1") (pin "7") (pinfunction "IO35_7") (pintype "bidirectional+no_connect"))
    )
    (net (code "69") (name "unconnected-(U1-SDI{slash}SD1-Pad22)") (class "Default")
      (node (ref "U1") (pin "22") (pinfunction "SDI/SD1_22") (pintype "bidirectional+no_connect"))
    )
    (net (code "70") (name "unconnected-(U1-SHD{slash}SD2-Pad17)") (class "Default")
      (node (ref "U1") (pin "17") (pinfunction "SHD/SD2_17") (pintype "bidirectional+no_connect"))
    )
    (net (code "71") (name "unconnected-(U1-SWP{slash}SD3-Pad18)") (class "Default")
      (node (ref "U1") (pin "18") (pinfunction "SWP/SD3_18") (pintype "bidirectional+no_connect"))
    )
    (net (code "72") (name "unconnected-(U3-*SUSPEND-Pad11)") (class "Default")
      (node (ref "U3") (pin "11") (pinfunction "*SUSPEND_11") (pintype "output+no_connect"))
    )
    (net (code "73") (name "unconnected-(U3-EPAD-Pad29)") (class "Default")
      (node (ref "U3") (pin "29") (pinfunction "EPAD_29") (pintype "passive"))
    )
    (net (code "74") (name "unconnected-(U3-NC-Pad10)") (class "Default")
      (node (ref "U3") (pin "10") (pinfunction "NC_10") (pintype "passive+no_connect"))
    )
    (net (code "75") (name "unconnected-(U3-NC-Pad13)") (class "Default")
      (node (ref "U3") (pin "13") (pinfunction "NC_13") (pintype "passive+no_connect"))
    )
    (net (code "76") (name "unconnected-(U3-NC-Pad14)") (class "Default")
      (node (ref "U3") (pin "14") (pinfunction "NC_14") (pintype "passive+no_connect"))
    )
    (net (code "77") (name "unconnected-(U3-NC-Pad15)") (class "Default")
      (node (ref "U3") (pin "15") (pinfunction "NC_15") (pintype "passive+no_connect"))
    )
    (net (code "78") (name "unconnected-(U3-NC-Pad16)") (class "Default")
      (node (ref "U3") (pin "16") (pinfunction "NC_16") (pintype "passive+no_connect"))
    )
    (net (code "79") (name "unconnected-(U3-NC-Pad17)") (class "Default")
      (node (ref "U3") (pin "17") (pinfunction "NC_17") (pintype "passive+no_connect"))
    )
    (net (code "80") (name "unconnected-(U3-NC-Pad19)") (class "Default")
      (node (ref "U3") (pin "19") (pinfunction "NC_19") (pintype "passive+no_connect"))
    )
    (net (code "81") (name "unconnected-(U3-NC-Pad20)") (class "Default")
      (node (ref "U3") (pin "20") (pinfunction "NC_20") (pintype "passive+no_connect"))
    )
    (net (code "82") (name "unconnected-(U3-NC-Pad21)") (class "Default")
      (node (ref "U3") (pin "21") (pinfunction "NC_21") (pintype "passive+no_connect"))
    )
    (net (code "83") (name "unconnected-(U3-NC-Pad22)") (class "Default")
      (node (ref "U3") (pin "22") (pinfunction "NC_22") (pintype "passive+no_connect"))
    )
    (net (code "84") (name "unconnected-(U3-NC{slash}VPP-Pad18)") (class "Default")
      (node (ref "U3") (pin "18") (pinfunction "NC/VPP_18") (pintype "bidirectional+no_connect"))
    )
    (net (code "85") (name "unconnected-(U3-SUSPEND-Pad12)") (class "Default")
      (node (ref "U3") (pin "12") (pinfunction "SUSPEND_12") (pintype "output+no_connect"))
    )
    (net (code "86") (name "unconnected-(U4-NC-Pad8)") (class "Default")
      (node (ref "U4") (pin "8") (pinfunction "NC_8") (pintype "passive"))
    )
    (net (code "87") (name "unconnected-(U4-OFS_NULL-Pad1)") (class "Default")
      (node (ref "U4") (pin "1") (pinfunction "OFS_NULL_1") (pintype "passive"))
    )
    (net (code "88") (name "unconnected-(U4-OFS_NULL-Pad5)") (class "Default")
      (node (ref "U4") (pin "5") (pinfunction "OFS_NULL_5") (pintype "passive"))
    )
    (net (code "89") (name "unconnected-(U5-NC-Pad8)") (class "Default")
      (node (ref "U5") (pin "8") (pinfunction "NC_8") (pintype "passive"))
    )
    (net (code "90") (name "unconnected-(U5-OFS_NULL-Pad1)") (class "Default")
      (node (ref "U5") (pin "1") (pinfunction "OFS_NULL_1") (pintype "passive"))
    )
    (net (code "91") (name "unconnected-(U5-OFS_NULL-Pad5)") (class "Default")
      (node (ref "U5") (pin "5") (pinfunction "OFS_NULL_5") (pintype "passive"))
    )
  )
)
